# 06_POWER.net
KiCad netlist of a schematic drawn in Altium Designer
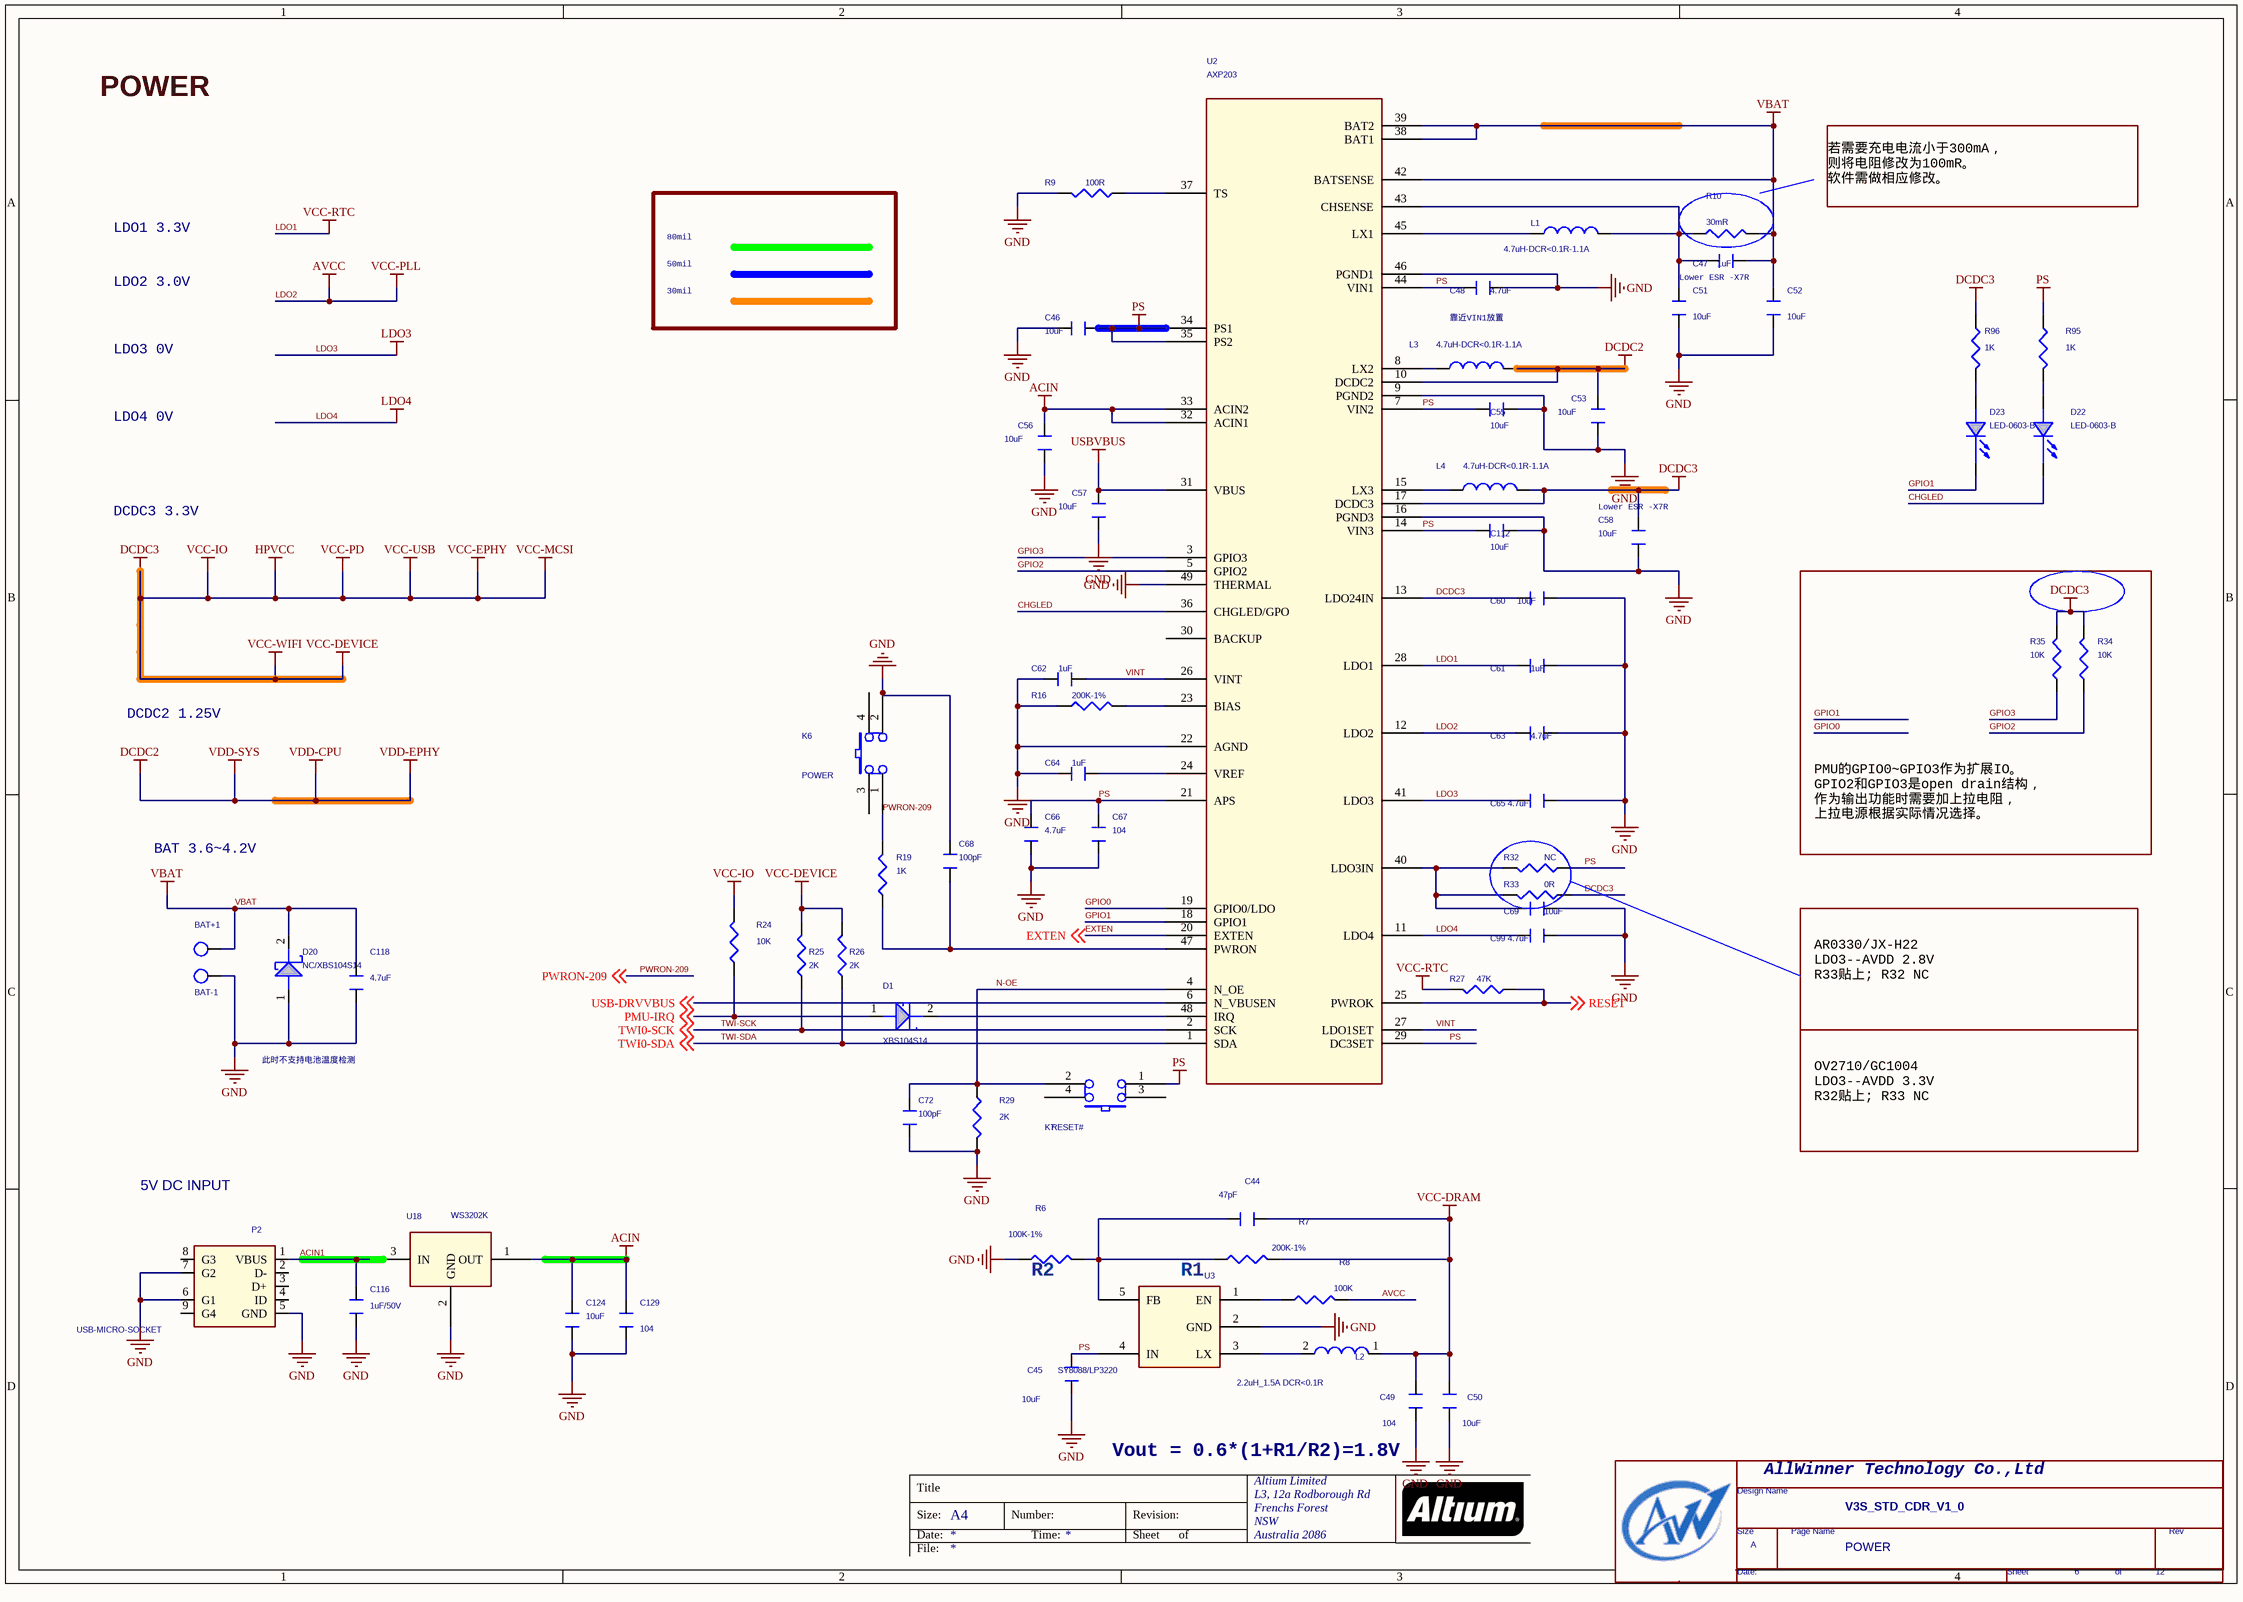
[diagram p0: 06 POWER.SchDoc]

(export (version "E")
  (design (tool "Eeschema 10.0.6"))
  (components
    (comp (ref "BAT+1") (value "VCC-3V") (footprint "BAT_SMD") (libsource (lib "*") (part "T_POINT_R")))
    (comp (ref "BAT-1") (value "VCC-3V") (footprint "BAT_SMD") (libsource (lib "*") (part "T_POINT_R")))
    (comp (ref "C44") (value "47pF") (footprint "C0402") (libsource (lib "*") (part "CAPACITOR_1")))
    (comp (ref "C45") (value "10uF") (footprint "C0603") (libsource (lib "*") (part "CAPACITOR_3")))
    (comp (ref "C46") (value "10uF") (footprint "C0603") (libsource (lib "*") (part "CAPACITOR_0_Dup2")))
    (comp (ref "C47") (value "1uF") (footprint "C0402") (libsource (lib "*") (part "CAPACITOR_0_Dup2")))
    (comp (ref "C48") (value "4.7uF") (footprint "C0402") (libsource (lib "*") (part "CAPACITOR_0_Dup2")))
    (comp (ref "C49") (value "104") (footprint "C0402") (libsource (lib "*") (part "CAPACITOR_1")))
    (comp (ref "C50") (value "10uF") (footprint "C0603") (libsource (lib "*") (part "CAPACITOR_3")))
    (comp (ref "C51") (value "10uF") (footprint "C0603") (libsource (lib "*") (part "CAPACITOR_0_Dup2")))
    (comp (ref "C52") (value "10uF") (footprint "C0603") (libsource (lib "*") (part "CAPACITOR_0_Dup2")))
    (comp (ref "C53") (value "10uF") (footprint "C0603") (libsource (lib "*") (part "CAPACITOR_0_Dup2")))
    (comp (ref "C55") (value "10uF") (footprint "C0603") (libsource (lib "*") (part "CAPACITOR_0_Dup2")))
    (comp (ref "C56") (value "10uF") (footprint "C0603") (libsource (lib "*") (part "CAPACITOR_0_Dup2")))
    (comp (ref "C57") (value "10uF") (footprint "C0603") (libsource (lib "*") (part "CAPACITOR_0_Dup2")))
    (comp (ref "C58") (value "10uF") (footprint "C0603") (libsource (lib "*") (part "CAPACITOR_0_Dup2")))
    (comp (ref "C60") (value "10uF") (footprint "C0603") (libsource (lib "*") (part "CAPACITOR_0_Dup2")))
    (comp (ref "C61") (value "1uF") (footprint "C0402") (libsource (lib "*") (part "CAPACITOR_0_Dup2")))
    (comp (ref "C62") (value "1uF") (footprint "C0402") (libsource (lib "*") (part "CAPACITOR_0_Dup2")))
    (comp (ref "C63") (value "4.7uF") (footprint "C0402") (libsource (lib "*") (part "CAPACITOR_0_Dup2")))
    (comp (ref "C64") (value "1uF") (footprint "C0402") (libsource (lib "*") (part "CAPACITOR_0_Dup2")))
    (comp (ref "C65") (value "4.7uF") (footprint "C0402") (libsource (lib "*") (part "CAPACITOR_0_Dup2")))
    (comp (ref "C66") (value "4.7uF") (footprint "C0402") (libsource (lib "*") (part "CAPACITOR_0_Dup2")))
    (comp (ref "C67") (value "104") (footprint "C0402") (libsource (lib "*") (part "CAPACITOR_0_Dup2")))
    (comp (ref "C68") (value "100pF") (footprint "C0402") (libsource (lib "*") (part "CAPACITOR_1")))
    (comp (ref "C69") (value "10uF") (footprint "C0603") (libsource (lib "*") (part "CAPACITOR_0_Dup2")))
    (comp (ref "C72") (value "100pF") (footprint "C0402") (libsource (lib "*") (part "CAPACITOR_1")))
    (comp (ref "C99") (value "4.7uF") (footprint "C0402") (libsource (lib "*") (part "CAPACITOR_0_Dup2")))
    (comp (ref "C112") (value "10uF") (footprint "C0603") (libsource (lib "*") (part "CAPACITOR_0_Dup2")))
    (comp (ref "C116") (value "1uF/50V") (footprint "C0603") (libsource (lib "*") (part "CAPACITOR_0_Dup2")))
    (comp (ref "C118") (value "4.7uF") (footprint "C0402") (libsource (lib "*") (part "CAPACITOR_Dup1")))
    (comp (ref "C124") (value "10uF") (footprint "C0603") (libsource (lib "*") (part "CAPACITOR_3")))
    (comp (ref "C129") (value "104") (footprint "C0402") (libsource (lib "*") (part "CAPACITOR_Dup1")))
    (comp (ref "D1")
      (value "XBS104S14")
      (footprint "SOD123")
      (description "RoHS 1.0 Ampere Schottky Barrier Rectifiers  SOD-123")
      (libsource (lib "*") (part "DIODE SCHOTTKY_0"))
    )
    (comp (ref "D20")
      (value "NC/XBS104S14")
      (footprint "SOD123")
      (libsource (lib "*") (part "DIODE_SCHOTTKY"))
    )
    (comp (ref "D22") (value "LED-0603-B") (footprint "0805") (libsource (lib "*") (part "LED")))
    (comp (ref "D23") (value "LED-0603-B") (footprint "0805") (libsource (lib "*") (part "LED")))
    (comp (ref "K6") (value "POWER") (footprint "SW4") (libsource (lib "*") (part "SW_PUSH_1")))
    (comp (ref "K7") (value "RESET#") (footprint "SW4") (libsource (lib "*") (part "SW_PUSH_0")))
    (comp (ref "L1")
      (value "4.7uH-DCR<0.1R-1.1A")
      (footprint "CD32")
      (libsource (lib "*") (part "INDUCTOR_1"))
    )
    (comp (ref "L2")
      (value "2.2uH_1.5A DCR<0.1R")
      (footprint "CD32")
      (libsource (lib "*") (part "INDUCTOR_Dup1"))
    )
    (comp (ref "L3")
      (value "4.7uH-DCR<0.1R-1.1A")
      (footprint "CD32")
      (libsource (lib "") (part "INDUCTOR_1_1"))
    )
    (comp (ref "L4")
      (value "4.7uH-DCR<0.1R-1.1A")
      (footprint "CD32")
      (libsource (lib "") (part "INDUCTOR_1_1"))
    )
    (comp (ref "P2")
      (value "USB-MICRO-SOCKET")
      (footprint "USB_MINI_AB")
      (libsource (lib "*") (part "USB_MINI_SOCKET_2"))
    )
    (comp (ref "R6") (value "100K-1%") (footprint "R0402") (libsource (lib "*") (part "R_Dup4")))
    (comp (ref "R7") (value "200K-1%") (footprint "R0402") (libsource (lib "*") (part "R_Dup4")))
    (comp (ref "R8") (value "100K") (footprint "R0402") (libsource (lib "*") (part "R_Dup4")))
    (comp (ref "R9") (value "100R") (footprint "R0402") (libsource (lib "*") (part "R_Dup4")))
    (comp (ref "R10") (value "30mR") (footprint "R0603") (libsource (lib "*") (part "R_Dup2")))
    (comp (ref "R16") (value "200K-1%") (footprint "R0402") (libsource (lib "*") (part "R_Dup4")))
    (comp (ref "R19") (value "1K") (footprint "R0402") (libsource (lib "*") (part "R_Dup3")))
    (comp (ref "R24") (value "10K") (footprint "R0402") (libsource (lib "*") (part "R_Dup4")))
    (comp (ref "R25") (value "2K") (footprint "R0402") (libsource (lib "*") (part "R_Dup4")))
    (comp (ref "R26") (value "2K") (footprint "R0402") (libsource (lib "*") (part "R_Dup4")))
    (comp (ref "R27") (value "47K") (footprint "R0402") (libsource (lib "*") (part "R_Dup4")))
    (comp (ref "R29") (value "2K") (footprint "R0402") (libsource (lib "*") (part "R_Dup4")))
    (comp (ref "R32") (value "NC") (footprint "R0402") (libsource (lib "*") (part "R_Dup4")))
    (comp (ref "R33") (value "0R") (footprint "R0402") (libsource (lib "*") (part "R_Dup4")))
    (comp (ref "R34") (value "10K") (footprint "R0402") (libsource (lib "*") (part "R_Dup4")))
    (comp (ref "R35") (value "10K") (footprint "R0402") (libsource (lib "*") (part "R_Dup4")))
    (comp (ref "R95") (value "1K") (footprint "R0402") (libsource (lib "*") (part "R_Dup4")))
    (comp (ref "R96") (value "1K") (footprint "R0402") (libsource (lib "*") (part "R_Dup4")))
    (comp (ref "U2") (value "AXP203") (footprint "QFN48") (libsource (lib "*") (part "AW1612_0")))
    (comp (ref "U3") (value "SY8088/LP3220") (footprint "TSOT-23-6") (libsource (lib "*") (part "RT9293B_0")))
    (comp (ref "U18") (value "WS3202K") (footprint "SOT-89-3L") (libsource (lib "*") (part "WS3202K_0")))
  )
  (nets
    (net (code "1") (name "/ACIN1") (class "Default")
      (node (ref "C116") (pin "2") (pinfunction "2_2") (pintype "passive"))
      (node (ref "P2") (pin "1") (pinfunction "VBUS_1") (pintype "passive"))
      (node (ref "U18") (pin "3") (pinfunction "IN_3") (pintype "passive"))
    )
    (net (code "2") (name "/CHGLED") (class "Default")
      (node (ref "D22") (pin "2") (pinfunction "CATHODE_2") (pintype "passive"))
      (node (ref "U2") (pin "36") (pinfunction "CHGLED/GPO_36") (pintype "passive"))
    )
    (net (code "3") (name "/GPIO0") (class "Default")
      (node (ref "U2") (pin "19") (pinfunction "GPIO0/LDO_19") (pintype "passive"))
    )
    (net (code "4") (name "/GPIO1") (class "Default")
      (node (ref "D23") (pin "2") (pinfunction "CATHODE_2") (pintype "passive"))
      (node (ref "U2") (pin "18") (pinfunction "GPIO1_18") (pintype "passive"))
    )
    (net (code "5") (name "/GPIO2") (class "Default")
      (node (ref "R34") (pin "1") (pinfunction "1_1") (pintype "passive"))
      (node (ref "U2") (pin "5") (pinfunction "GPIO2_5") (pintype "passive"))
    )
    (net (code "6") (name "/GPIO3") (class "Default")
      (node (ref "R35") (pin "1") (pinfunction "1_1") (pintype "passive"))
      (node (ref "U2") (pin "3") (pinfunction "GPIO3_3") (pintype "passive"))
    )
    (net (code "7") (name "/N-OE") (class "Default")
      (node (ref "C72") (pin "1") (pinfunction "1_1") (pintype "passive"))
      (node (ref "K7") (pin "2") (pinfunction "2_2") (pintype "passive"))
      (node (ref "R29") (pin "1") (pinfunction "1_1") (pintype "passive"))
      (node (ref "U2") (pin "4") (pinfunction "N_OE_4") (pintype "passive"))
    )
    (net (code "8") (name "/VINT") (class "Default")
      (node (ref "C62") (pin "1") (pinfunction "1_1") (pintype "passive"))
      (node (ref "U2") (pin "26") (pinfunction "VINT_26") (pintype "passive"))
      (node (ref "U2") (pin "27") (pinfunction "LDO1SET_27") (pintype "passive"))
    )
    (net (code "9") (name "ACIN") (class "Default")
      (node (ref "C124") (pin "1") (pinfunction "1_1") (pintype "passive"))
      (node (ref "C129") (pin "2") (pinfunction "2_2") (pintype "passive"))
      (node (ref "C56") (pin "1") (pinfunction "1_1") (pintype "passive"))
      (node (ref "U18") (pin "1") (pinfunction "OUT_1") (pintype "passive"))
      (node (ref "U2") (pin "32") (pinfunction "ACIN1_32") (pintype "passive"))
      (node (ref "U2") (pin "33") (pinfunction "ACIN2_33") (pintype "passive"))
    )
    (net (code "10") (name "AVCC") (class "Default")
      (node (ref "C63") (pin "1") (pinfunction "1_1") (pintype "passive"))
      (node (ref "R8") (pin "1") (pinfunction "1_1") (pintype "passive"))
      (node (ref "U2") (pin "12") (pinfunction "LDO2_12") (pintype "passive"))
    )
    (net (code "11") (name "DCDC2") (class "Default")
      (node (ref "C53") (pin "1") (pinfunction "1_1") (pintype "passive"))
      (node (ref "L3") (pin "2") (pinfunction "2_2") (pintype "passive"))
      (node (ref "U2") (pin "10") (pinfunction "DCDC2_10") (pintype "passive"))
    )
    (net (code "12") (name "DCDC3") (class "Default")
      (node (ref "C58") (pin "1") (pinfunction "1_1") (pintype "passive"))
      (node (ref "C60") (pin "1") (pinfunction "1_1") (pintype "passive"))
      (node (ref "L4") (pin "2") (pinfunction "2_2") (pintype "passive"))
      (node (ref "R24") (pin "2") (pinfunction "2_2") (pintype "passive"))
      (node (ref "R25") (pin "2") (pinfunction "2_2") (pintype "passive"))
      (node (ref "R26") (pin "2") (pinfunction "2_2") (pintype "passive"))
      (node (ref "R33") (pin "1") (pinfunction "1_1") (pintype "passive"))
      (node (ref "R34") (pin "2") (pinfunction "2_2") (pintype "passive"))
      (node (ref "R35") (pin "2") (pinfunction "2_2") (pintype "passive"))
      (node (ref "R96") (pin "1") (pinfunction "1_1") (pintype "passive"))
      (node (ref "U2") (pin "13") (pinfunction "LDO24IN_13") (pintype "passive"))
      (node (ref "U2") (pin "17") (pinfunction "DCDC3_17") (pintype "passive"))
    )
    (net (code "13") (name "EXTEN") (class "Default")
      (node (ref "U2") (pin "20") (pinfunction "EXTEN_20") (pintype "passive"))
    )
    (net (code "14") (name "GND") (class "Default")
      (node (ref "BAT-1") (pin "1") (pinfunction "TP_1") (pintype "passive"))
      (node (ref "C112") (pin "2") (pinfunction "2_2") (pintype "passive"))
      (node (ref "C116") (pin "1") (pinfunction "1_1") (pintype "passive"))
      (node (ref "C118") (pin "1") (pinfunction "1_1") (pintype "passive"))
      (node (ref "C124") (pin "2") (pinfunction "2_2") (pintype "passive"))
      (node (ref "C129") (pin "1") (pinfunction "1_1") (pintype "passive"))
      (node (ref "C45") (pin "2") (pinfunction "2_2") (pintype "passive"))
      (node (ref "C46") (pin "1") (pinfunction "1_1") (pintype "passive"))
      (node (ref "C48") (pin "2") (pinfunction "2_2") (pintype "passive"))
      (node (ref "C49") (pin "2") (pinfunction "2_2") (pintype "passive"))
      (node (ref "C50") (pin "2") (pinfunction "2_2") (pintype "passive"))
      (node (ref "C51") (pin "2") (pinfunction "2_2") (pintype "passive"))
      (node (ref "C52") (pin "2") (pinfunction "2_2") (pintype "passive"))
      (node (ref "C53") (pin "2") (pinfunction "2_2") (pintype "passive"))
      (node (ref "C55") (pin "2") (pinfunction "2_2") (pintype "passive"))
      (node (ref "C56") (pin "2") (pinfunction "2_2") (pintype "passive"))
      (node (ref "C57") (pin "2") (pinfunction "2_2") (pintype "passive"))
      (node (ref "C58") (pin "2") (pinfunction "2_2") (pintype "passive"))
      (node (ref "C60") (pin "2") (pinfunction "2_2") (pintype "passive"))
      (node (ref "C61") (pin "1") (pinfunction "1_1") (pintype "passive"))
      (node (ref "C62") (pin "2") (pinfunction "2_2") (pintype "passive"))
      (node (ref "C63") (pin "2") (pinfunction "2_2") (pintype "passive"))
      (node (ref "C64") (pin "1") (pinfunction "1_1") (pintype "passive"))
      (node (ref "C65") (pin "1") (pinfunction "1_1") (pintype "passive"))
      (node (ref "C66") (pin "2") (pinfunction "2_2") (pintype "passive"))
      (node (ref "C67") (pin "1") (pinfunction "1_1") (pintype "passive"))
      (node (ref "C68") (pin "1") (pinfunction "1_1") (pintype "passive"))
      (node (ref "C69") (pin "2") (pinfunction "2_2") (pintype "passive"))
      (node (ref "C72") (pin "2") (pinfunction "2_2") (pintype "passive"))
      (node (ref "C99") (pin "1") (pinfunction "1_1") (pintype "passive"))
      (node (ref "D20") (pin "1") (pinfunction "1_1") (pintype "passive"))
      (node (ref "K6") (pin "2") (pinfunction "2_2") (pintype "passive"))
      (node (ref "P2") (pin "5") (pinfunction "GND_5") (pintype "passive"))
      (node (ref "P2") (pin "6") (pinfunction "G1_6") (pintype "passive"))
      (node (ref "P2") (pin "7") (pinfunction "G2_7") (pintype "passive"))
      (node (ref "R16") (pin "1") (pinfunction "1_1") (pintype "passive"))
      (node (ref "R29") (pin "2") (pinfunction "2_2") (pintype "passive"))
      (node (ref "R6") (pin "2") (pinfunction "2_2") (pintype "passive"))
      (node (ref "R9") (pin "2") (pinfunction "2_2") (pintype "passive"))
      (node (ref "U18") (pin "2") (pinfunction "GND_2") (pintype "passive"))
      (node (ref "U2") (pin "16") (pinfunction "PGND3_16") (pintype "passive"))
      (node (ref "U2") (pin "22") (pinfunction "AGND_22") (pintype "passive"))
      (node (ref "U2") (pin "46") (pinfunction "PGND1_46") (pintype "passive"))
      (node (ref "U2") (pin "49") (pinfunction "THERMAL_49") (pintype "passive"))
      (node (ref "U2") (pin "9") (pinfunction "PGND2_9") (pintype "passive"))
      (node (ref "U3") (pin "2") (pinfunction "GND_2") (pintype "passive"))
    )
    (net (code "15") (name "LDO3") (class "Default")
      (node (ref "C65") (pin "2") (pinfunction "2_2") (pintype "passive"))
      (node (ref "U2") (pin "41") (pinfunction "LDO3_41") (pintype "passive"))
    )
    (net (code "16") (name "LDO4") (class "Default")
      (node (ref "C99") (pin "2") (pinfunction "2_2") (pintype "passive"))
      (node (ref "U2") (pin "11") (pinfunction "LDO4_11") (pintype "passive"))
    )
    (net (code "17") (name "Net-(D22-ANODE)") (class "Default")
      (node (ref "D22") (pin "1") (pinfunction "ANODE_1") (pintype "passive"))
      (node (ref "R95") (pin "2") (pinfunction "2_2") (pintype "passive"))
    )
    (net (code "18") (name "Net-(D23-ANODE)") (class "Default")
      (node (ref "D23") (pin "1") (pinfunction "ANODE_1") (pintype "passive"))
      (node (ref "R96") (pin "2") (pinfunction "2_2") (pintype "passive"))
    )
    (net (code "19") (name "Net-(U2-BIAS)") (class "Default")
      (node (ref "R16") (pin "2") (pinfunction "2_2") (pintype "passive"))
      (node (ref "U2") (pin "23") (pinfunction "BIAS_23") (pintype "passive"))
    )
    (net (code "20") (name "Net-(U2-CHSENSE)") (class "Default")
      (node (ref "C47") (pin "1") (pinfunction "1_1") (pintype "passive"))
      (node (ref "C51") (pin "1") (pinfunction "1_1") (pintype "passive"))
      (node (ref "L1") (pin "1") (pinfunction "1_1") (pintype "passive"))
      (node (ref "R10") (pin "2") (pinfunction "2_2") (pintype "passive"))
      (node (ref "U2") (pin "43") (pinfunction "CHSENSE_43") (pintype "passive"))
    )
    (net (code "21") (name "Net-(U2-IRQ)") (class "Default")
      (node (ref "D1") (pin "2") (pinfunction "2_2") (pintype "passive"))
      (node (ref "U2") (pin "48") (pinfunction "IRQ_48") (pintype "passive"))
    )
    (net (code "22") (name "Net-(U2-LDO3IN)") (class "Default")
      (node (ref "C69") (pin "1") (pinfunction "1_1") (pintype "passive"))
      (node (ref "R32") (pin "2") (pinfunction "2_2") (pintype "passive"))
      (node (ref "R33") (pin "2") (pinfunction "2_2") (pintype "passive"))
      (node (ref "U2") (pin "40") (pinfunction "LDO3IN_40") (pintype "passive"))
    )
    (net (code "23") (name "Net-(U2-LX1)") (class "Default")
      (node (ref "L1") (pin "2") (pinfunction "2_2") (pintype "passive"))
      (node (ref "U2") (pin "45") (pinfunction "LX1_45") (pintype "passive"))
    )
    (net (code "24") (name "Net-(U2-LX2)") (class "Default")
      (node (ref "L3") (pin "1") (pinfunction "1_1") (pintype "passive"))
      (node (ref "U2") (pin "8") (pinfunction "LX2_8") (pintype "passive"))
    )
    (net (code "25") (name "Net-(U2-LX3)") (class "Default")
      (node (ref "L4") (pin "1") (pinfunction "1_1") (pintype "passive"))
      (node (ref "U2") (pin "15") (pinfunction "LX3_15") (pintype "passive"))
    )
    (net (code "26") (name "Net-(U2-PWRON)") (class "Default")
      (node (ref "C68") (pin "2") (pinfunction "2_2") (pintype "passive"))
      (node (ref "R19") (pin "1") (pinfunction "1_1") (pintype "passive"))
      (node (ref "U2") (pin "47") (pinfunction "PWRON_47") (pintype "passive"))
    )
    (net (code "27") (name "Net-(U2-TS)") (class "Default")
      (node (ref "R9") (pin "1") (pinfunction "1_1") (pintype "passive"))
      (node (ref "U2") (pin "37") (pinfunction "TS_37") (pintype "passive"))
    )
    (net (code "28") (name "Net-(U2-VREF)") (class "Default")
      (node (ref "C64") (pin "2") (pinfunction "2_2") (pintype "passive"))
      (node (ref "U2") (pin "24") (pinfunction "VREF_24") (pintype "passive"))
    )
    (net (code "29") (name "Net-(U3-EN)") (class "Default")
      (node (ref "R8") (pin "2") (pinfunction "2_2") (pintype "passive"))
      (node (ref "U3") (pin "1") (pinfunction "EN_1") (pintype "passive"))
    )
    (net (code "30") (name "Net-(U3-FB)") (class "Default")
      (node (ref "C44") (pin "2") (pinfunction "2_2") (pintype "passive"))
      (node (ref "R6") (pin "1") (pinfunction "1_1") (pintype "passive"))
      (node (ref "R7") (pin "2") (pinfunction "2_2") (pintype "passive"))
      (node (ref "U3") (pin "5") (pinfunction "FB_5") (pintype "passive"))
    )
    (net (code "31") (name "Net-(U3-LX)") (class "Default")
      (node (ref "L2") (pin "2") (pinfunction "2_2") (pintype "passive"))
      (node (ref "U3") (pin "3") (pinfunction "LX_3") (pintype "passive"))
    )
    (net (code "32") (name "PMU-IRQ") (class "Default")
      (node (ref "D1") (pin "1") (pinfunction "1_1") (pintype "passive"))
      (node (ref "R24") (pin "1") (pinfunction "1_1") (pintype "passive"))
    )
    (net (code "33") (name "PS") (class "Default")
      (node (ref "C112") (pin "1") (pinfunction "1_1") (pintype "passive"))
      (node (ref "C45") (pin "1") (pinfunction "1_1") (pintype "passive"))
      (node (ref "C46") (pin "2") (pinfunction "2_2") (pintype "passive"))
      (node (ref "C48") (pin "1") (pinfunction "1_1") (pintype "passive"))
      (node (ref "C55") (pin "1") (pinfunction "1_1") (pintype "passive"))
      (node (ref "C66") (pin "1") (pinfunction "1_1") (pintype "passive"))
      (node (ref "C67") (pin "2") (pinfunction "2_2") (pintype "passive"))
      (node (ref "K7") (pin "1") (pinfunction "1_1") (pintype "passive"))
      (node (ref "R32") (pin "1") (pinfunction "1_1") (pintype "passive"))
      (node (ref "R95") (pin "1") (pinfunction "1_1") (pintype "passive"))
      (node (ref "U2") (pin "14") (pinfunction "VIN3_14") (pintype "passive"))
      (node (ref "U2") (pin "21") (pinfunction "APS_21") (pintype "passive"))
      (node (ref "U2") (pin "29") (pinfunction "DC3SET_29") (pintype "passive"))
      (node (ref "U2") (pin "34") (pinfunction "PS1_34") (pintype "passive"))
      (node (ref "U2") (pin "35") (pinfunction "PS2_35") (pintype "passive"))
      (node (ref "U2") (pin "44") (pinfunction "VIN1_44") (pintype "passive"))
      (node (ref "U2") (pin "7") (pinfunction "VIN2_7") (pintype "passive"))
      (node (ref "U3") (pin "4") (pinfunction "IN_4") (pintype "passive"))
    )
    (net (code "34") (name "PWRON-209") (class "Default")
      (node (ref "K6") (pin "1") (pinfunction "1_1") (pintype "passive"))
      (node (ref "R19") (pin "2") (pinfunction "2_2") (pintype "passive"))
    )
    (net (code "35") (name "RESET") (class "Default")
      (node (ref "R27") (pin "1") (pinfunction "1_1") (pintype "passive"))
      (node (ref "U2") (pin "25") (pinfunction "PWROK_25") (pintype "passive"))
    )
    (net (code "36") (name "TWI0-SCK") (class "Default")
      (node (ref "R25") (pin "1") (pinfunction "1_1") (pintype "passive"))
      (node (ref "U2") (pin "2") (pinfunction "SCK_2") (pintype "passive"))
    )
    (net (code "37") (name "TWI0-SDA") (class "Default")
      (node (ref "R26") (pin "1") (pinfunction "1_1") (pintype "passive"))
      (node (ref "U2") (pin "1") (pinfunction "SDA_1") (pintype "passive"))
    )
    (net (code "38") (name "USB-DRVVBUS") (class "Default")
      (node (ref "U2") (pin "6") (pinfunction "N_VBUSEN_6") (pintype "passive"))
    )
    (net (code "39") (name "USBVBUS") (class "Default")
      (node (ref "C57") (pin "1") (pinfunction "1_1") (pintype "passive"))
      (node (ref "U2") (pin "31") (pinfunction "VBUS_31") (pintype "passive"))
    )
    (net (code "40") (name "VBAT") (class "Default")
      (node (ref "BAT+1") (pin "1") (pinfunction "TP_1") (pintype "passive"))
      (node (ref "C118") (pin "2") (pinfunction "2_2") (pintype "passive"))
      (node (ref "C47") (pin "2") (pinfunction "2_2") (pintype "passive"))
      (node (ref "C52") (pin "1") (pinfunction "1_1") (pintype "passive"))
      (node (ref "D20") (pin "2") (pinfunction "2_2") (pintype "passive"))
      (node (ref "R10") (pin "1") (pinfunction "1_1") (pintype "passive"))
      (node (ref "U2") (pin "38") (pinfunction "BAT1_38") (pintype "passive"))
      (node (ref "U2") (pin "39") (pinfunction "BAT2_39") (pintype "passive"))
      (node (ref "U2") (pin "42") (pinfunction "BATSENSE_42") (pintype "passive"))
    )
    (net (code "41") (name "VCC-DRAM") (class "Default")
      (node (ref "C44") (pin "1") (pinfunction "1_1") (pintype "passive"))
      (node (ref "C49") (pin "1") (pinfunction "1_1") (pintype "passive"))
      (node (ref "C50") (pin "1") (pinfunction "1_1") (pintype "passive"))
      (node (ref "L2") (pin "1") (pinfunction "1_1") (pintype "passive"))
      (node (ref "R7") (pin "1") (pinfunction "1_1") (pintype "passive"))
    )
    (net (code "42") (name "VCC-RTC") (class "Default")
      (node (ref "C61") (pin "2") (pinfunction "2_2") (pintype "passive"))
      (node (ref "R27") (pin "2") (pinfunction "2_2") (pintype "passive"))
      (node (ref "U2") (pin "28") (pinfunction "LDO1_28") (pintype "passive"))
    )
    (net (code "43") (name "unconnected-(K6-Pad3)") (class "Default")
      (node (ref "K6") (pin "3") (pinfunction "3_3") (pintype "passive"))
    )
    (net (code "44") (name "unconnected-(K6-Pad4)") (class "Default")
      (node (ref "K6") (pin "4") (pinfunction "4_4") (pintype "passive"))
    )
    (net (code "45") (name "unconnected-(K7-Pad3)") (class "Default")
      (node (ref "K7") (pin "3") (pinfunction "3_3") (pintype "passive"))
    )
    (net (code "46") (name "unconnected-(K7-Pad4)") (class "Default")
      (node (ref "K7") (pin "4") (pinfunction "4_4") (pintype "passive"))
    )
    (net (code "47") (name "unconnected-(P2-D+-Pad3)") (class "Default")
      (node (ref "P2") (pin "3") (pinfunction "D+_3") (pintype "passive"))
    )
    (net (code "48") (name "unconnected-(P2-D--Pad2)") (class "Default")
      (node (ref "P2") (pin "2") (pinfunction "D-_2") (pintype "passive"))
    )
    (net (code "49") (name "unconnected-(P2-G3-Pad8)") (class "Default")
      (node (ref "P2") (pin "8") (pinfunction "G3_8") (pintype "passive"))
    )
    (net (code "50") (name "unconnected-(P2-G4-Pad9)") (class "Default")
      (node (ref "P2") (pin "9") (pinfunction "G4_9") (pintype "passive"))
    )
    (net (code "51") (name "unconnected-(P2-ID-Pad4)") (class "Default")
      (node (ref "P2") (pin "4") (pinfunction "ID_4") (pintype "passive"))
    )
    (net (code "52") (name "unconnected-(U2-BACKUP-Pad30)") (class "Default")
      (node (ref "U2") (pin "30") (pinfunction "BACKUP_30") (pintype "passive"))
    )
  )
)
